# shiitakevmctl.net
KiCad netlist of a schematic drawn in EAGLE
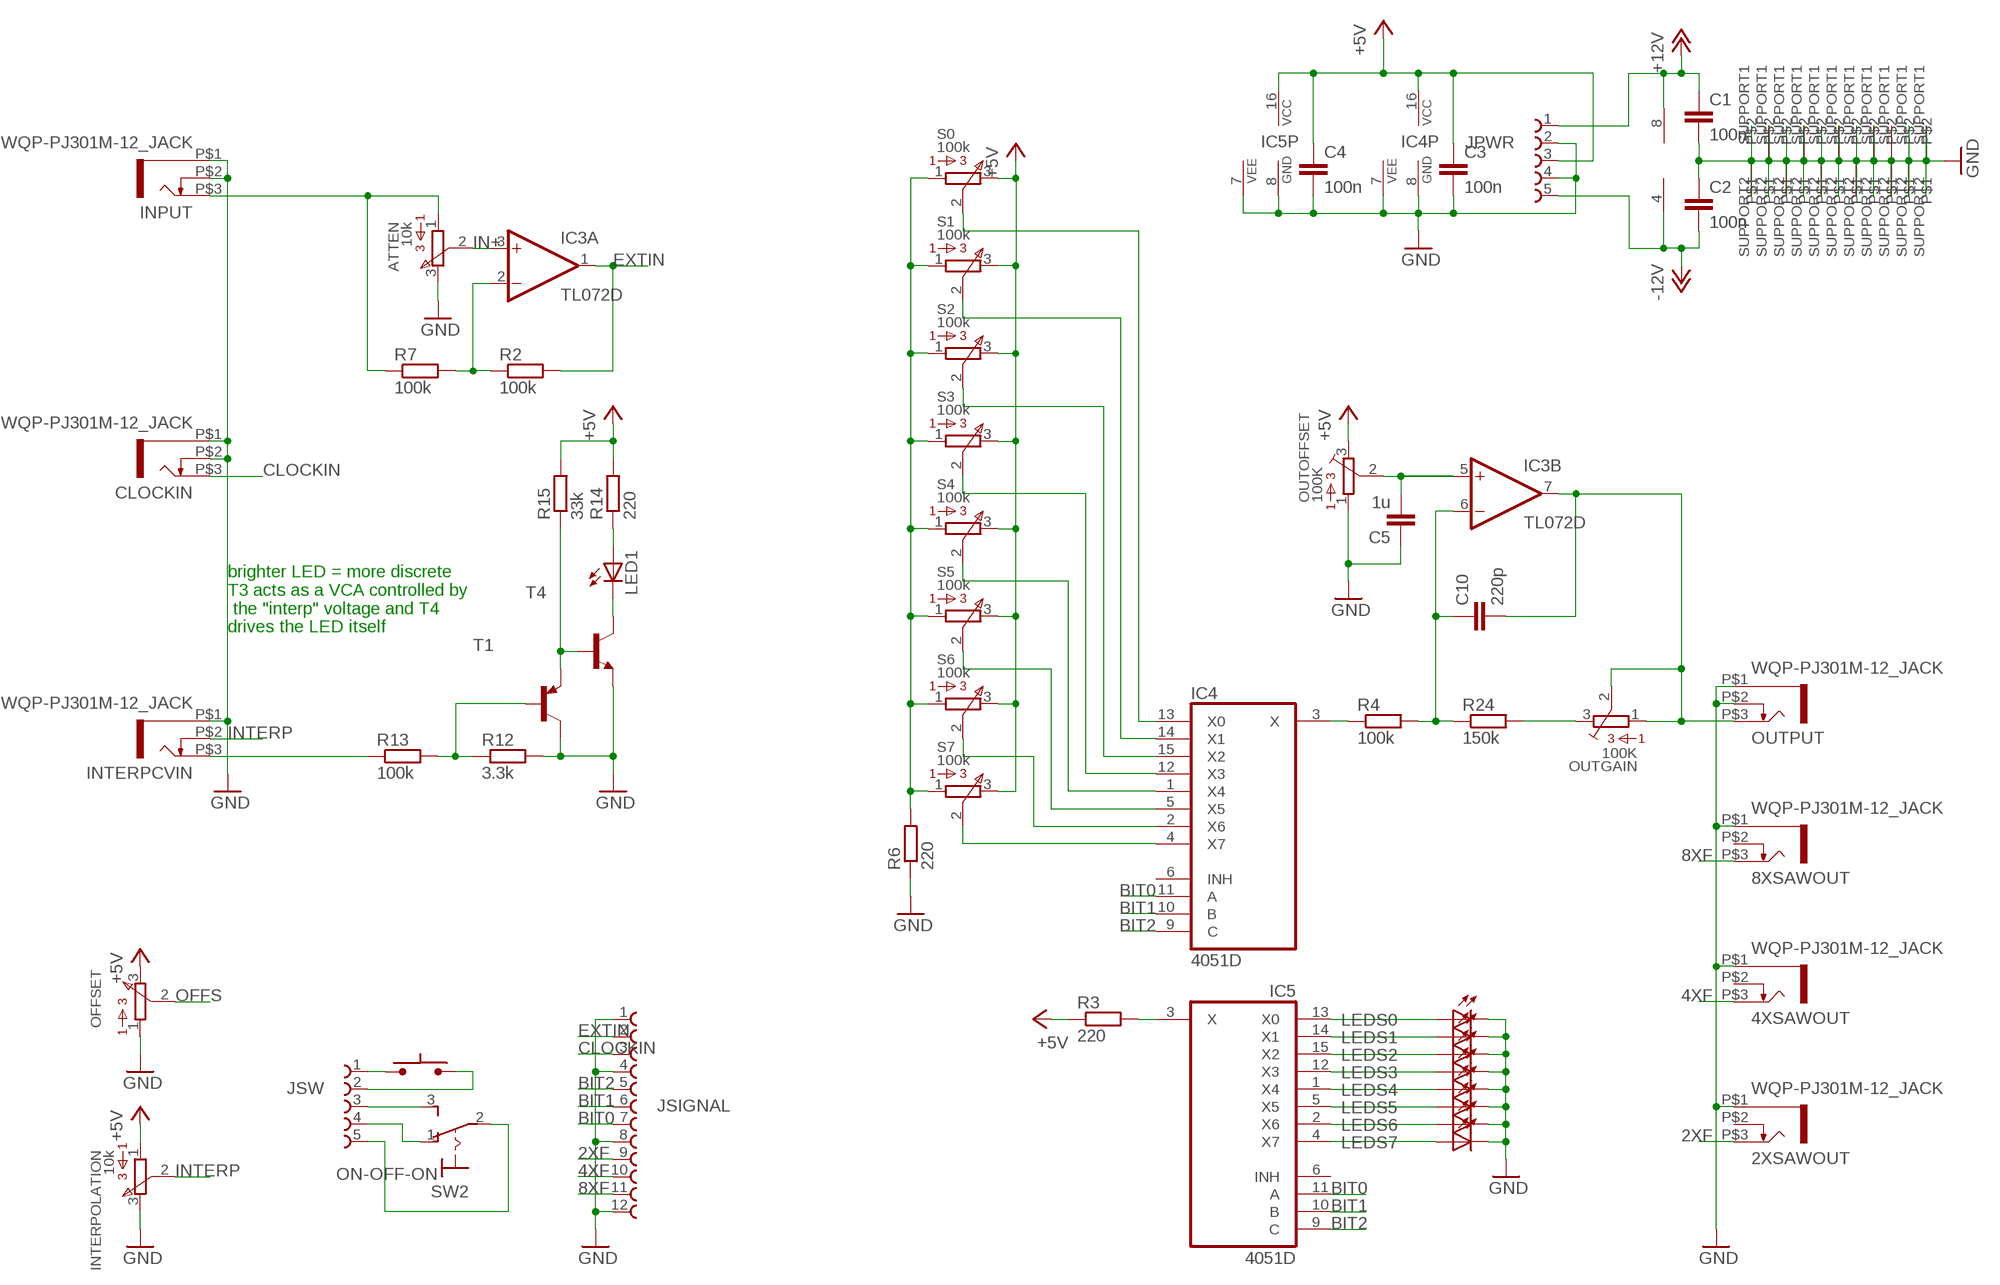
[diagram p0: schematic, sheet 1]

(export (version "E")
  (design (tool "Eeschema 10.0.6"))
  (components
    (comp (ref "2XSAWOUT")
      (value "WQP-PJ301M-12_JACK")
      (footprint "eagle-import:WQP-PJ301M-12_JACK")
      (libsource (lib "eagle-import") (part "WQP-PJ301M-12_JACK"))
    )
    (comp (ref "4XSAWOUT")
      (value "WQP-PJ301M-12_JACK")
      (footprint "eagle-import:WQP-PJ301M-12_JACK")
      (libsource (lib "eagle-import") (part "WQP-PJ301M-12_JACK"))
    )
    (comp (ref "8XSAWOUT")
      (value "WQP-PJ301M-12_JACK")
      (footprint "eagle-import:WQP-PJ301M-12_JACK")
      (libsource (lib "eagle-import") (part "WQP-PJ301M-12_JACK"))
    )
    (comp (ref "ATTEN")
      (value "10k")
      (footprint "eagle-import:308")
      (libsource (lib "eagle-import") (part "308/309"))
    )
    (comp (ref "C1")
      (value "100n")
      (footprint "eagle-import:C1206")
      (libsource (lib "eagle-import") (part "C-EUC1206"))
    )
    (comp (ref "C2")
      (value "100n")
      (footprint "eagle-import:C1206")
      (libsource (lib "eagle-import") (part "C-EUC1206"))
    )
    (comp (ref "C3")
      (value "100n")
      (footprint "eagle-import:C1206")
      (libsource (lib "eagle-import") (part "C-EUC1206"))
    )
    (comp (ref "C4")
      (value "100n")
      (footprint "eagle-import:C1206")
      (libsource (lib "eagle-import") (part "C-EUC1206"))
    )
    (comp (ref "C5")
      (value "1u")
      (footprint "eagle-import:C1206")
      (libsource (lib "eagle-import") (part "C-EUC1206"))
    )
    (comp (ref "C10")
      (value "220p")
      (footprint "eagle-import:C1206")
      (libsource (lib "eagle-import") (part "C-EUC1206"))
    )
    (comp (ref "CLOCKIN")
      (value "WQP-PJ301M-12_JACK")
      (footprint "eagle-import:WQP-PJ301M-12_JACK")
      (libsource (lib "eagle-import") (part "WQP-PJ301M-12_JACK"))
    )
    (comp (ref "IC3")
      (value "TL072D")
      (footprint "eagle-import:SO08")
      (libsource (lib "eagle-import") (part "TL072D"))
    )
    (comp (ref "IC4")
      (value "4051D")
      (footprint "eagle-import:SO16")
      (libsource (lib "eagle-import") (part "4051D"))
    )
    (comp (ref "IC5")
      (value "4051D")
      (footprint "eagle-import:SO16")
      (libsource (lib "eagle-import") (part "4051D"))
    )
    (comp (ref "INPUT")
      (value "WQP-PJ301M-12_JACK")
      (footprint "eagle-import:WQP-PJ301M-12_JACK")
      (libsource (lib "eagle-import") (part "WQP-PJ301M-12_JACK"))
    )
    (comp (ref "INTERPCVIN")
      (value "WQP-PJ301M-12_JACK")
      (footprint "eagle-import:WQP-PJ301M-12_JACK")
      (libsource (lib "eagle-import") (part "WQP-PJ301M-12_JACK"))
    )
    (comp (ref "INTERPOLATION")
      (value "10k")
      (footprint "eagle-import:308")
      (libsource (lib "eagle-import") (part "308/309"))
    )
    (comp (ref "JPWR")
      (value "61300511121")
      (footprint "eagle-import:61300511121")
      (libsource (lib "eagle-import") (part "61300511121"))
    )
    (comp (ref "JSIGNAL")
      (value "61301211121")
      (footprint "eagle-import:61301211121")
      (libsource (lib "eagle-import") (part "61301211121"))
    )
    (comp (ref "JSW")
      (value "61300511121")
      (footprint "eagle-import:61300511121")
      (libsource (lib "eagle-import") (part "61300511121"))
    )
    (comp (ref "LED1")
      (value "LEDCHIPLED_0805")
      (footprint "eagle-import:CHIPLED_0805")
      (libsource (lib "eagle-import") (part "LEDCHIPLED_0805"))
    )
    (comp (ref "LEDS0")
      (value "LED3MM")
      (footprint "eagle-import:LED3MM")
      (libsource (lib "eagle-import") (part "LED3MM"))
    )
    (comp (ref "LEDS1")
      (value "LED3MM")
      (footprint "eagle-import:LED3MM")
      (libsource (lib "eagle-import") (part "LED3MM"))
    )
    (comp (ref "LEDS2")
      (value "LED3MM")
      (footprint "eagle-import:LED3MM")
      (libsource (lib "eagle-import") (part "LED3MM"))
    )
    (comp (ref "LEDS3")
      (value "LED3MM")
      (footprint "eagle-import:LED3MM")
      (libsource (lib "eagle-import") (part "LED3MM"))
    )
    (comp (ref "LEDS4")
      (value "LED3MM")
      (footprint "eagle-import:LED3MM")
      (libsource (lib "eagle-import") (part "LED3MM"))
    )
    (comp (ref "LEDS5")
      (value "LED3MM")
      (footprint "eagle-import:LED3MM")
      (libsource (lib "eagle-import") (part "LED3MM"))
    )
    (comp (ref "LEDS6")
      (value "LED3MM")
      (footprint "eagle-import:LED3MM")
      (libsource (lib "eagle-import") (part "LED3MM"))
    )
    (comp (ref "LEDS7")
      (value "LED3MM")
      (footprint "eagle-import:LED3MM")
      (libsource (lib "eagle-import") (part "LED3MM"))
    )
    (comp (ref "OFFSET")
      (value "308/309")
      (footprint "eagle-import:308")
      (libsource (lib "eagle-import") (part "308/309"))
    )
    (comp (ref "OUTGAIN")
      (value "100K")
      (footprint "eagle-import:3386C")
      (libsource (lib "eagle-import") (part "3386-C"))
    )
    (comp (ref "OUTOFFSET")
      (value "100K")
      (footprint "eagle-import:3386C")
      (libsource (lib "eagle-import") (part "3386-C"))
    )
    (comp (ref "OUTPUT")
      (value "WQP-PJ301M-12_JACK")
      (footprint "eagle-import:WQP-PJ301M-12_JACK")
      (libsource (lib "eagle-import") (part "WQP-PJ301M-12_JACK"))
    )
    (comp (ref "R2")
      (value "100k")
      (footprint "eagle-import:R1206")
      (libsource (lib "eagle-import") (part "R-EU_R1206"))
    )
    (comp (ref "R3")
      (value "220")
      (footprint "eagle-import:R1206")
      (libsource (lib "eagle-import") (part "R-EU_R1206"))
    )
    (comp (ref "R4")
      (value "100k")
      (footprint "eagle-import:R1206")
      (libsource (lib "eagle-import") (part "R-EU_R1206"))
    )
    (comp (ref "R6")
      (value "220")
      (footprint "eagle-import:R1206")
      (libsource (lib "eagle-import") (part "R-EU_R1206"))
    )
    (comp (ref "R7")
      (value "100k")
      (footprint "eagle-import:R1206")
      (libsource (lib "eagle-import") (part "R-EU_R1206"))
    )
    (comp (ref "R12")
      (value "3.3k")
      (footprint "eagle-import:R1206")
      (libsource (lib "eagle-import") (part "R-EU_R1206"))
    )
    (comp (ref "R13")
      (value "100k")
      (footprint "eagle-import:R1206")
      (libsource (lib "eagle-import") (part "R-EU_R1206"))
    )
    (comp (ref "R14")
      (value "220")
      (footprint "eagle-import:R1206")
      (libsource (lib "eagle-import") (part "R-EU_R1206"))
    )
    (comp (ref "R15")
      (value "33k")
      (footprint "eagle-import:R1206")
      (libsource (lib "eagle-import") (part "R-EU_R1206"))
    )
    (comp (ref "R24")
      (value "150k")
      (footprint "eagle-import:R1206")
      (libsource (lib "eagle-import") (part "R-EU_R1206"))
    )
    (comp (ref "S0")
      (value "100k")
      (footprint "eagle-import:308")
      (libsource (lib "eagle-import") (part "308/309"))
    )
    (comp (ref "S1")
      (value "100k")
      (footprint "eagle-import:308")
      (libsource (lib "eagle-import") (part "308/309"))
    )
    (comp (ref "S2")
      (value "100k")
      (footprint "eagle-import:308")
      (libsource (lib "eagle-import") (part "308/309"))
    )
    (comp (ref "S3")
      (value "100k")
      (footprint "eagle-import:308")
      (libsource (lib "eagle-import") (part "308/309"))
    )
    (comp (ref "S4")
      (value "100k")
      (footprint "eagle-import:308")
      (libsource (lib "eagle-import") (part "308/309"))
    )
    (comp (ref "S5")
      (value "100k")
      (footprint "eagle-import:308")
      (libsource (lib "eagle-import") (part "308/309"))
    )
    (comp (ref "S6")
      (value "100k")
      (footprint "eagle-import:308")
      (libsource (lib "eagle-import") (part "308/309"))
    )
    (comp (ref "S7")
      (value "100k")
      (footprint "eagle-import:308")
      (libsource (lib "eagle-import") (part "308/309"))
    )
    (comp (ref "SW1")
      (value "PUSHSWITCH")
      (footprint "eagle-import:PUSHSWITCH")
      (libsource (lib "eagle-import") (part "PUSHSWITCH"))
    )
    (comp (ref "SW2")
      (value "ON-OFF-ON")
      (footprint "eagle-import:320-916")
      (libsource (lib "eagle-import") (part "320-916"))
    )
    (comp (ref "T1")
      (value "MMBT3906LT1-PNP-SOT23-BEC")
      (footprint "eagle-import:SOT23-BEC")
      (libsource (lib "eagle-import") (part "-PNP-SOT23-BECMMBT3906LT1"))
    )
    (comp (ref "T4")
      (value "MMBT3904LT1-NPN-SOT23-BEC")
      (footprint "eagle-import:SOT23-BEC")
      (libsource (lib "eagle-import") (part "-NPN-SOT23-BECMMBT3904LT1"))
    )
  )
  (nets
    (net (code "1") (name "+5V") (class "Default")
      (node (ref "C3") (pin "1") (pinfunction "1_1") (pintype "passive"))
      (node (ref "C4") (pin "1") (pinfunction "1_1") (pintype "passive"))
      (node (ref "IC4") (pin "16") (pinfunction "VCC_16") (pintype "power_in"))
      (node (ref "IC5") (pin "16") (pinfunction "VCC_16") (pintype "power_in"))
      (node (ref "INTERPOLATION") (pin "1") (pinfunction "1_1") (pintype "passive"))
      (node (ref "JPWR") (pin "3") (pinfunction "3_3") (pintype "passive"))
      (node (ref "OFFSET") (pin "3") (pinfunction "3_3") (pintype "passive"))
      (node (ref "OUTOFFSET") (pin "3") (pinfunction "3_3") (pintype "passive"))
      (node (ref "R14") (pin "2") (pinfunction "2_2") (pintype "passive"))
      (node (ref "R15") (pin "2") (pinfunction "2_2") (pintype "passive"))
      (node (ref "R3") (pin "1") (pinfunction "1_1") (pintype "passive"))
      (node (ref "S0") (pin "3") (pinfunction "3_3") (pintype "passive"))
      (node (ref "S1") (pin "3") (pinfunction "3_3") (pintype "passive"))
      (node (ref "S2") (pin "3") (pinfunction "3_3") (pintype "passive"))
      (node (ref "S3") (pin "3") (pinfunction "3_3") (pintype "passive"))
      (node (ref "S4") (pin "3") (pinfunction "3_3") (pintype "passive"))
      (node (ref "S5") (pin "3") (pinfunction "3_3") (pintype "passive"))
      (node (ref "S6") (pin "3") (pinfunction "3_3") (pintype "passive"))
      (node (ref "S7") (pin "3") (pinfunction "3_3") (pintype "passive"))
    )
    (net (code "2") (name "+12V") (class "Default")
      (node (ref "C1") (pin "1") (pinfunction "1_1") (pintype "passive"))
      (node (ref "IC3") (pin "8") (pinfunction "V+_8") (pintype "power_in"))
      (node (ref "JPWR") (pin "1") (pinfunction "1_1") (pintype "passive"))
    )
    (net (code "3") (name "-12V") (class "Default")
      (node (ref "C2") (pin "2") (pinfunction "2_2") (pintype "passive"))
      (node (ref "IC3") (pin "4") (pinfunction "V-_4") (pintype "power_in"))
      (node (ref "JPWR") (pin "5") (pinfunction "5_5") (pintype "passive"))
    )
    (net (code "4") (name "/2XF") (class "Default")
      (node (ref "2XSAWOUT") (pin "P$3") (pinfunction "2_P$3") (pintype "passive"))
      (node (ref "JSIGNAL") (pin "9") (pinfunction "9_9") (pintype "passive"))
    )
    (net (code "5") (name "/4XF") (class "Default")
      (node (ref "4XSAWOUT") (pin "P$3") (pinfunction "2_P$3") (pintype "passive"))
      (node (ref "JSIGNAL") (pin "10") (pinfunction "10_10") (pintype "passive"))
    )
    (net (code "6") (name "/8XF") (class "Default")
      (node (ref "8XSAWOUT") (pin "P$3") (pinfunction "2_P$3") (pintype "passive"))
      (node (ref "JSIGNAL") (pin "11") (pinfunction "11_11") (pintype "passive"))
    )
    (net (code "7") (name "/BIT0") (class "Default")
      (node (ref "IC4") (pin "11") (pinfunction "A_11") (pintype "input"))
      (node (ref "IC5") (pin "11") (pinfunction "A_11") (pintype "input"))
      (node (ref "JSIGNAL") (pin "7") (pinfunction "7_7") (pintype "passive"))
    )
    (net (code "8") (name "/BIT1") (class "Default")
      (node (ref "IC4") (pin "10") (pinfunction "B_10") (pintype "input"))
      (node (ref "IC5") (pin "10") (pinfunction "B_10") (pintype "input"))
      (node (ref "JSIGNAL") (pin "6") (pinfunction "6_6") (pintype "passive"))
    )
    (net (code "9") (name "/BIT2") (class "Default")
      (node (ref "IC4") (pin "9") (pinfunction "C_9") (pintype "input"))
      (node (ref "IC5") (pin "9") (pinfunction "C_9") (pintype "input"))
      (node (ref "JSIGNAL") (pin "5") (pinfunction "5_5") (pintype "passive"))
    )
    (net (code "10") (name "/CLOCKIN") (class "Default")
      (node (ref "CLOCKIN") (pin "P$3") (pinfunction "2_P$3") (pintype "passive"))
      (node (ref "JSIGNAL") (pin "3") (pinfunction "3_3") (pintype "passive"))
    )
    (net (code "11") (name "/EXTIN") (class "Default")
      (node (ref "IC3") (pin "1") (pinfunction "OUT_1") (pintype "output"))
      (node (ref "JSIGNAL") (pin "2") (pinfunction "2_2") (pintype "passive"))
      (node (ref "R2") (pin "2") (pinfunction "2_2") (pintype "passive"))
    )
    (net (code "12") (name "/IN+") (class "Default")
      (node (ref "ATTEN") (pin "2") (pinfunction "2_2") (pintype "passive"))
      (node (ref "IC3") (pin "3") (pinfunction "+IN_3") (pintype "input"))
    )
    (net (code "13") (name "/INTERP") (class "Default")
      (node (ref "INTERPCVIN") (pin "P$2") (pinfunction "3_P$2") (pintype "passive"))
      (node (ref "INTERPOLATION") (pin "2") (pinfunction "2_2") (pintype "passive"))
    )
    (net (code "14") (name "/OFFS") (class "Default")
      (node (ref "OFFSET") (pin "2") (pinfunction "2_2") (pintype "passive"))
    )
    (net (code "15") (name "GND") (class "Default")
      (node (ref "2XSAWOUT") (pin "P$1") (pinfunction "1_P$1") (pintype "passive"))
      (node (ref "4XSAWOUT") (pin "P$1") (pinfunction "1_P$1") (pintype "passive"))
      (node (ref "8XSAWOUT") (pin "P$1") (pinfunction "1_P$1") (pintype "passive"))
      (node (ref "ATTEN") (pin "3") (pinfunction "3_3") (pintype "passive"))
      (node (ref "ATTEN") (pin "SUPPORT2") (pinfunction "P$2_SUPPORT2") (pintype "bidirectional"))
      (node (ref "C1") (pin "2") (pinfunction "2_2") (pintype "passive"))
      (node (ref "C2") (pin "1") (pinfunction "1_1") (pintype "passive"))
      (node (ref "C3") (pin "2") (pinfunction "2_2") (pintype "passive"))
      (node (ref "C4") (pin "2") (pinfunction "2_2") (pintype "passive"))
      (node (ref "C5") (pin "1") (pinfunction "1_1") (pintype "passive"))
      (node (ref "CLOCKIN") (pin "P$1") (pinfunction "1_P$1") (pintype "passive"))
      (node (ref "CLOCKIN") (pin "P$2") (pinfunction "3_P$2") (pintype "passive"))
      (node (ref "IC4") (pin "7") (pinfunction "VEE_7") (pintype "power_in"))
      (node (ref "IC4") (pin "8") (pinfunction "GND_8") (pintype "power_in"))
      (node (ref "IC5") (pin "7") (pinfunction "VEE_7") (pintype "power_in"))
      (node (ref "IC5") (pin "8") (pinfunction "GND_8") (pintype "power_in"))
      (node (ref "INPUT") (pin "P$1") (pinfunction "1_P$1") (pintype "passive"))
      (node (ref "INPUT") (pin "P$2") (pinfunction "3_P$2") (pintype "passive"))
      (node (ref "INTERPCVIN") (pin "P$1") (pinfunction "1_P$1") (pintype "passive"))
      (node (ref "INTERPOLATION") (pin "3") (pinfunction "3_3") (pintype "passive"))
      (node (ref "INTERPOLATION") (pin "SUPPORT1") (pinfunction "P$1_SUPPORT1") (pintype "bidirectional"))
      (node (ref "INTERPOLATION") (pin "SUPPORT2") (pinfunction "P$2_SUPPORT2") (pintype "bidirectional"))
      (node (ref "JPWR") (pin "2") (pinfunction "2_2") (pintype "passive"))
      (node (ref "JPWR") (pin "4") (pinfunction "4_4") (pintype "passive"))
      (node (ref "JSIGNAL") (pin "1") (pinfunction "1_1") (pintype "passive"))
      (node (ref "JSIGNAL") (pin "12") (pinfunction "12_12") (pintype "passive"))
      (node (ref "JSIGNAL") (pin "4") (pinfunction "4_4") (pintype "passive"))
      (node (ref "JSIGNAL") (pin "8") (pinfunction "8_8") (pintype "passive"))
      (node (ref "LEDS0") (pin "K") (pinfunction "C_K") (pintype "passive"))
      (node (ref "LEDS1") (pin "K") (pinfunction "C_K") (pintype "passive"))
      (node (ref "LEDS2") (pin "K") (pinfunction "C_K") (pintype "passive"))
      (node (ref "LEDS3") (pin "K") (pinfunction "C_K") (pintype "passive"))
      (node (ref "LEDS4") (pin "K") (pinfunction "C_K") (pintype "passive"))
      (node (ref "LEDS5") (pin "K") (pinfunction "C_K") (pintype "passive"))
      (node (ref "LEDS6") (pin "K") (pinfunction "C_K") (pintype "passive"))
      (node (ref "LEDS7") (pin "K") (pinfunction "C_K") (pintype "passive"))
      (node (ref "OFFSET") (pin "1") (pinfunction "1_1") (pintype "passive"))
      (node (ref "OFFSET") (pin "SUPPORT1") (pinfunction "P$1_SUPPORT1") (pintype "bidirectional"))
      (node (ref "OFFSET") (pin "SUPPORT2") (pinfunction "P$2_SUPPORT2") (pintype "bidirectional"))
      (node (ref "OUTOFFSET") (pin "1") (pinfunction "1_1") (pintype "passive"))
      (node (ref "OUTPUT") (pin "P$1") (pinfunction "1_P$1") (pintype "passive"))
      (node (ref "OUTPUT") (pin "P$2") (pinfunction "3_P$2") (pintype "passive"))
      (node (ref "R12") (pin "2") (pinfunction "2_2") (pintype "passive"))
      (node (ref "R6") (pin "1") (pinfunction "1_1") (pintype "passive"))
      (node (ref "S0") (pin "SUPPORT1") (pinfunction "P$1_SUPPORT1") (pintype "bidirectional"))
      (node (ref "S0") (pin "SUPPORT2") (pinfunction "P$2_SUPPORT2") (pintype "bidirectional"))
      (node (ref "S1") (pin "SUPPORT1") (pinfunction "P$1_SUPPORT1") (pintype "bidirectional"))
      (node (ref "S1") (pin "SUPPORT2") (pinfunction "P$2_SUPPORT2") (pintype "bidirectional"))
      (node (ref "S2") (pin "SUPPORT1") (pinfunction "P$1_SUPPORT1") (pintype "bidirectional"))
      (node (ref "S2") (pin "SUPPORT2") (pinfunction "P$2_SUPPORT2") (pintype "bidirectional"))
      (node (ref "S3") (pin "SUPPORT1") (pinfunction "P$1_SUPPORT1") (pintype "bidirectional"))
      (node (ref "S3") (pin "SUPPORT2") (pinfunction "P$2_SUPPORT2") (pintype "bidirectional"))
      (node (ref "S4") (pin "SUPPORT1") (pinfunction "P$1_SUPPORT1") (pintype "bidirectional"))
      (node (ref "S4") (pin "SUPPORT2") (pinfunction "P$2_SUPPORT2") (pintype "bidirectional"))
      (node (ref "S5") (pin "SUPPORT1") (pinfunction "P$1_SUPPORT1") (pintype "bidirectional"))
      (node (ref "S5") (pin "SUPPORT2") (pinfunction "P$2_SUPPORT2") (pintype "bidirectional"))
      (node (ref "S6") (pin "SUPPORT1") (pinfunction "P$1_SUPPORT1") (pintype "bidirectional"))
      (node (ref "S6") (pin "SUPPORT2") (pinfunction "P$2_SUPPORT2") (pintype "bidirectional"))
      (node (ref "S7") (pin "SUPPORT1") (pinfunction "P$1_SUPPORT1") (pintype "bidirectional"))
      (node (ref "S7") (pin "SUPPORT2") (pinfunction "P$2_SUPPORT2") (pintype "bidirectional"))
      (node (ref "T1") (pin "C") (pinfunction "C_C") (pintype "passive"))
      (node (ref "T4") (pin "E") (pinfunction "E_E") (pintype "passive"))
    )
    (net (code "16") (name "Net-(IC3A--IN)") (class "Default")
      (node (ref "IC3") (pin "2") (pinfunction "-IN_2") (pintype "input"))
      (node (ref "R2") (pin "1") (pinfunction "1_1") (pintype "passive"))
      (node (ref "R7") (pin "2") (pinfunction "2_2") (pintype "passive"))
    )
    (net (code "17") (name "Net-(IC3B-+IN)") (class "Default")
      (node (ref "C5") (pin "2") (pinfunction "2_2") (pintype "passive"))
      (node (ref "IC3") (pin "5") (pinfunction "+IN_5") (pintype "input"))
      (node (ref "OUTOFFSET") (pin "2") (pinfunction "2_2") (pintype "passive"))
    )
    (net (code "18") (name "Net-(IC3B--IN)") (class "Default")
      (node (ref "C10") (pin "1") (pinfunction "1_1") (pintype "passive"))
      (node (ref "IC3") (pin "6") (pinfunction "-IN_6") (pintype "input"))
      (node (ref "R24") (pin "1") (pinfunction "1_1") (pintype "passive"))
      (node (ref "R4") (pin "2") (pinfunction "2_2") (pintype "passive"))
    )
    (net (code "19") (name "Net-(IC3B-OUT)") (class "Default")
      (node (ref "C10") (pin "2") (pinfunction "2_2") (pintype "passive"))
      (node (ref "IC3") (pin "7") (pinfunction "OUT_7") (pintype "output"))
      (node (ref "OUTGAIN") (pin "1") (pinfunction "1_1") (pintype "passive"))
      (node (ref "OUTGAIN") (pin "2") (pinfunction "2_2") (pintype "passive"))
      (node (ref "OUTPUT") (pin "P$3") (pinfunction "2_P$3") (pintype "passive"))
    )
    (net (code "20") (name "Net-(IC4A-X)") (class "Default")
      (node (ref "IC4") (pin "3") (pinfunction "X_3") (pintype "bidirectional"))
      (node (ref "R4") (pin "1") (pinfunction "1_1") (pintype "passive"))
    )
    (net (code "21") (name "Net-(IC4A-X0)") (class "Default")
      (node (ref "IC4") (pin "13") (pinfunction "X0_13") (pintype "bidirectional"))
      (node (ref "S0") (pin "2") (pinfunction "2_2") (pintype "passive"))
    )
    (net (code "22") (name "Net-(IC4A-X1)") (class "Default")
      (node (ref "IC4") (pin "14") (pinfunction "X1_14") (pintype "bidirectional"))
      (node (ref "S1") (pin "2") (pinfunction "2_2") (pintype "passive"))
    )
    (net (code "23") (name "Net-(IC4A-X2)") (class "Default")
      (node (ref "IC4") (pin "15") (pinfunction "X2_15") (pintype "bidirectional"))
      (node (ref "S2") (pin "2") (pinfunction "2_2") (pintype "passive"))
    )
    (net (code "24") (name "Net-(IC4A-X3)") (class "Default")
      (node (ref "IC4") (pin "12") (pinfunction "X3_12") (pintype "bidirectional"))
      (node (ref "S3") (pin "2") (pinfunction "2_2") (pintype "passive"))
    )
    (net (code "25") (name "Net-(IC4A-X4)") (class "Default")
      (node (ref "IC4") (pin "1") (pinfunction "X4_1") (pintype "bidirectional"))
      (node (ref "S4") (pin "2") (pinfunction "2_2") (pintype "passive"))
    )
    (net (code "26") (name "Net-(IC4A-X5)") (class "Default")
      (node (ref "IC4") (pin "5") (pinfunction "X5_5") (pintype "bidirectional"))
      (node (ref "S5") (pin "2") (pinfunction "2_2") (pintype "passive"))
    )
    (net (code "27") (name "Net-(IC4A-X6)") (class "Default")
      (node (ref "IC4") (pin "2") (pinfunction "X6_2") (pintype "bidirectional"))
      (node (ref "S6") (pin "2") (pinfunction "2_2") (pintype "passive"))
    )
    (net (code "28") (name "Net-(IC4A-X7)") (class "Default")
      (node (ref "IC4") (pin "4") (pinfunction "X7_4") (pintype "bidirectional"))
      (node (ref "S7") (pin "2") (pinfunction "2_2") (pintype "passive"))
    )
    (net (code "29") (name "Net-(IC5A-X)") (class "Default")
      (node (ref "IC5") (pin "3") (pinfunction "X_3") (pintype "bidirectional"))
      (node (ref "R3") (pin "2") (pinfunction "2_2") (pintype "passive"))
    )
    (net (code "30") (name "Net-(IC5A-X0)") (class "Default")
      (node (ref "IC5") (pin "13") (pinfunction "X0_13") (pintype "bidirectional"))
      (node (ref "LEDS0") (pin "A") (pinfunction "A_A") (pintype "passive"))
    )
    (net (code "31") (name "Net-(IC5A-X1)") (class "Default")
      (node (ref "IC5") (pin "14") (pinfunction "X1_14") (pintype "bidirectional"))
      (node (ref "LEDS1") (pin "A") (pinfunction "A_A") (pintype "passive"))
    )
    (net (code "32") (name "Net-(IC5A-X2)") (class "Default")
      (node (ref "IC5") (pin "15") (pinfunction "X2_15") (pintype "bidirectional"))
      (node (ref "LEDS2") (pin "A") (pinfunction "A_A") (pintype "passive"))
    )
    (net (code "33") (name "Net-(IC5A-X3)") (class "Default")
      (node (ref "IC5") (pin "12") (pinfunction "X3_12") (pintype "bidirectional"))
      (node (ref "LEDS3") (pin "A") (pinfunction "A_A") (pintype "passive"))
    )
    (net (code "34") (name "Net-(IC5A-X4)") (class "Default")
      (node (ref "IC5") (pin "1") (pinfunction "X4_1") (pintype "bidirectional"))
      (node (ref "LEDS4") (pin "A") (pinfunction "A_A") (pintype "passive"))
    )
    (net (code "35") (name "Net-(IC5A-X5)") (class "Default")
      (node (ref "IC5") (pin "5") (pinfunction "X5_5") (pintype "bidirectional"))
      (node (ref "LEDS5") (pin "A") (pinfunction "A_A") (pintype "passive"))
    )
    (net (code "36") (name "Net-(IC5A-X6)") (class "Default")
      (node (ref "IC5") (pin "2") (pinfunction "X6_2") (pintype "bidirectional"))
      (node (ref "LEDS6") (pin "A") (pinfunction "A_A") (pintype "passive"))
    )
    (net (code "37") (name "Net-(IC5A-X7)") (class "Default")
      (node (ref "IC5") (pin "4") (pinfunction "X7_4") (pintype "bidirectional"))
      (node (ref "LEDS7") (pin "A") (pinfunction "A_A") (pintype "passive"))
    )
    (net (code "38") (name "Net-(INPUT-2)") (class "Default")
      (node (ref "ATTEN") (pin "1") (pinfunction "1_1") (pintype "passive"))
      (node (ref "INPUT") (pin "P$3") (pinfunction "2_P$3") (pintype "passive"))
      (node (ref "R7") (pin "1") (pinfunction "1_1") (pintype "passive"))
    )
    (net (code "39") (name "Net-(INTERPCVIN-2)") (class "Default")
      (node (ref "INTERPCVIN") (pin "P$3") (pinfunction "2_P$3") (pintype "passive"))
      (node (ref "R13") (pin "1") (pinfunction "1_1") (pintype "passive"))
    )
    (net (code "40") (name "Net-(JSW-Pad1)") (class "Default")
      (node (ref "JSW") (pin "1") (pinfunction "1_1") (pintype "passive"))
      (node (ref "SW1") (pin "P$1") (pinfunction "P$1_P$1") (pintype "bidirectional"))
    )
    (net (code "41") (name "Net-(JSW-Pad2)") (class "Default")
      (node (ref "JSW") (pin "2") (pinfunction "2_2") (pintype "passive"))
      (node (ref "SW1") (pin "P$2") (pinfunction "P$2_P$2") (pintype "bidirectional"))
    )
    (net (code "42") (name "Net-(LED1-PadA)") (class "Default")
      (node (ref "LED1") (pin "A") (pinfunction "A_A") (pintype "passive"))
      (node (ref "R14") (pin "1") (pinfunction "1_1") (pintype "passive"))
    )
    (net (code "43") (name "Net-(LED1-PadC)") (class "Default")
      (node (ref "LED1") (pin "C") (pinfunction "C_C") (pintype "passive"))
      (node (ref "T4") (pin "C") (pinfunction "C_C") (pintype "passive"))
    )
    (net (code "44") (name "Net-(OUTGAIN-Pad3)") (class "Default")
      (node (ref "OUTGAIN") (pin "3") (pinfunction "3_3") (pintype "passive"))
      (node (ref "R24") (pin "2") (pinfunction "2_2") (pintype "passive"))
    )
    (net (code "45") (name "Net-(R6-Pad2)") (class "Default")
      (node (ref "R6") (pin "2") (pinfunction "2_2") (pintype "passive"))
      (node (ref "S0") (pin "1") (pinfunction "1_1") (pintype "passive"))
      (node (ref "S1") (pin "1") (pinfunction "1_1") (pintype "passive"))
      (node (ref "S2") (pin "1") (pinfunction "1_1") (pintype "passive"))
      (node (ref "S3") (pin "1") (pinfunction "1_1") (pintype "passive"))
      (node (ref "S4") (pin "1") (pinfunction "1_1") (pintype "passive"))
      (node (ref "S5") (pin "1") (pinfunction "1_1") (pintype "passive"))
      (node (ref "S6") (pin "1") (pinfunction "1_1") (pintype "passive"))
      (node (ref "S7") (pin "1") (pinfunction "1_1") (pintype "passive"))
    )
    (net (code "46") (name "Net-(R12-Pad1)") (class "Default")
      (node (ref "R12") (pin "1") (pinfunction "1_1") (pintype "passive"))
      (node (ref "R13") (pin "2") (pinfunction "2_2") (pintype "passive"))
      (node (ref "T1") (pin "B") (pinfunction "B_B") (pintype "passive"))
    )
    (net (code "47") (name "Net-(R15-Pad1)") (class "Default")
      (node (ref "R15") (pin "1") (pinfunction "1_1") (pintype "passive"))
      (node (ref "T1") (pin "E") (pinfunction "E_E") (pintype "passive"))
      (node (ref "T4") (pin "B") (pinfunction "B_B") (pintype "passive"))
    )
    (net (code "48") (name "Net-(SW2-O)") (class "Default")
      (node (ref "JSW") (pin "4") (pinfunction "4_4") (pintype "passive"))
      (node (ref "SW2") (pin "1") (pinfunction "O_1") (pintype "passive"))
    )
    (net (code "49") (name "Net-(SW2-P)") (class "Default")
      (node (ref "JSW") (pin "5") (pinfunction "5_5") (pintype "passive"))
      (node (ref "SW2") (pin "2") (pinfunction "P_2") (pintype "passive"))
    )
    (net (code "50") (name "Net-(SW2-S)") (class "Default")
      (node (ref "JSW") (pin "3") (pinfunction "3_3") (pintype "passive"))
      (node (ref "SW2") (pin "3") (pinfunction "S_3") (pintype "passive"))
    )
    (net (code "51") (name "unconnected-(2XSAWOUT-3-PadP$2)") (class "Default")
      (node (ref "2XSAWOUT") (pin "P$2") (pinfunction "3_P$2") (pintype "passive"))
    )
    (net (code "52") (name "unconnected-(4XSAWOUT-3-PadP$2)") (class "Default")
      (node (ref "4XSAWOUT") (pin "P$2") (pinfunction "3_P$2") (pintype "passive"))
    )
    (net (code "53") (name "unconnected-(8XSAWOUT-3-PadP$2)") (class "Default")
      (node (ref "8XSAWOUT") (pin "P$2") (pinfunction "3_P$2") (pintype "passive"))
    )
    (net (code "54") (name "unconnected-(ATTENB-P$1-PadSUPPORT1)") (class "Default")
      (node (ref "ATTEN") (pin "SUPPORT1") (pinfunction "P$1_SUPPORT1") (pintype "bidirectional"))
    )
    (net (code "55") (name "unconnected-(IC4A-INH-Pad6)") (class "Default")
      (node (ref "IC4") (pin "6") (pinfunction "INH_6") (pintype "input"))
    )
    (net (code "56") (name "unconnected-(IC5A-INH-Pad6)") (class "Default")
      (node (ref "IC5") (pin "6") (pinfunction "INH_6") (pintype "input"))
    )
  )
)
